# Pag5_Perifericos.net
KiCad netlist of a schematic drawn in Altium Designer
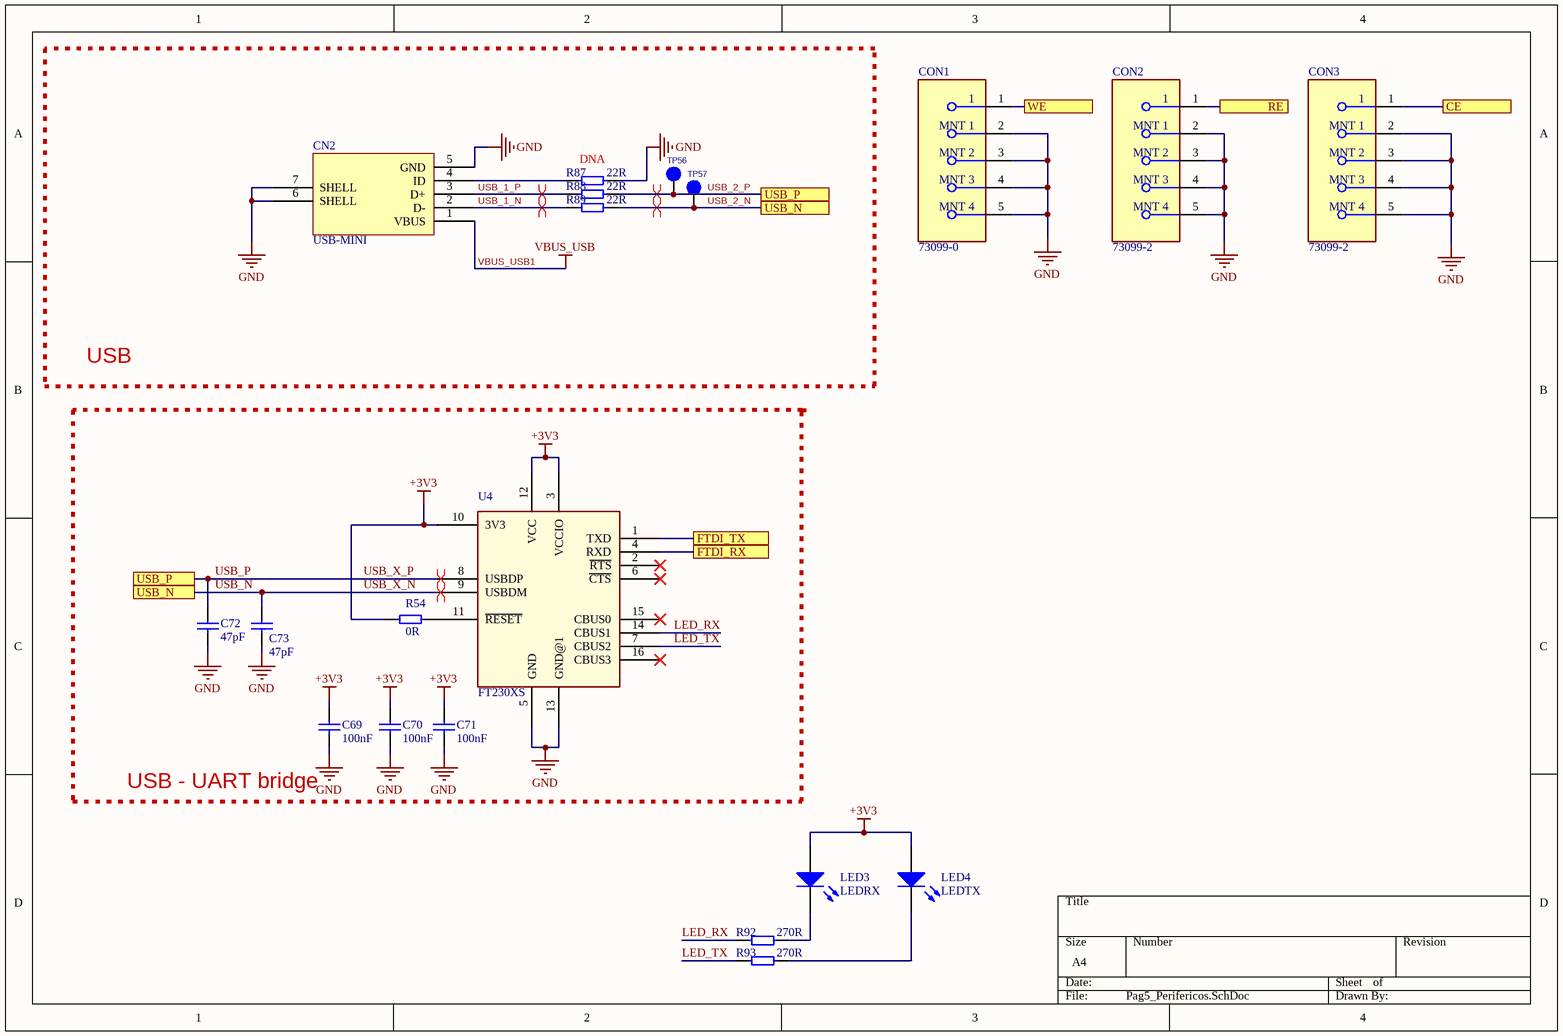
[diagram p0: Pag5_Perifericos.SchDoc]

(export (version "E")
  (design (tool "Eeschema 10.0.6"))
  (components
    (comp (ref "C69")
      (value "100nF")
      (footprint "0603")
      (description "Multilayer Ceramic Capacitors MLCC - SMD/SMT 100nF 16V 0603 10%")
      (fields (field (name "MANUFACTURER") "KEMET") (field (name "MPN") "C0603C104K4RACTU"))
      (libsource (lib "LIBSCH_PULLUP") (part "Cap"))
    )
    (comp (ref "C70")
      (value "100nF")
      (footprint "0603")
      (description "Multilayer Ceramic Capacitors MLCC - SMD/SMT 100nF 16V 0603 10%")
      (fields (field (name "MANUFACTURER") "KEMET") (field (name "MPN") "C0603C104K4RACTU"))
      (libsource (lib "LIBSCH_PULLUP") (part "Cap"))
    )
    (comp (ref "C71")
      (value "100nF")
      (footprint "0603")
      (description "Multilayer Ceramic Capacitors MLCC - SMD/SMT 100nF 16V 0603 10%")
      (fields (field (name "MANUFACTURER") "KEMET") (field (name "MPN") "C0603C104K4RACTU"))
      (libsource (lib "LIBSCH_PULLUP") (part "Cap"))
    )
    (comp (ref "C72")
      (value "47pF")
      (footprint "0603")
      (description "Multilayer Ceramic Capacitors MLCC - SMD/SMT 47pF 0603 25V 5%")
      (fields (field (name "MANUFACTURER") "Vishay") (field (name "MPN") "VJ0603A470JXXPW1BC"))
      (libsource (lib "LIBSCH_PULLUP") (part "Cap"))
    )
    (comp (ref "C73")
      (value "47pF")
      (footprint "0603")
      (description "Multilayer Ceramic Capacitors MLCC - SMD/SMT 47pF 0603 25V 5%")
      (fields (field (name "MANUFACTURER") "Vishay") (field (name "MPN") "VJ0603A470JXXPW1BC"))
      (libsource (lib "LIBSCH_PULLUP") (part "Cap"))
    )
    (comp (ref "CN2")
      (value "USB-MINI")
      (footprint "TE_2172034-1")
      (description "Standard LEDs - SMD 0603 SMT CHIP LED 572nm")
      (fields (field (name "MPN") "2172034-1") (field (name "MANUFACTURER") "TE Connectivity AMP Connectors"))
      (libsource (lib "LIBSCH_PULLUP") (part "USB-MINI"))
    )
    (comp (ref "CON1")
      (value "73099-0")
      (footprint "FP-73099-0-MFG")
      (description "R/A 4MM MOUNTG SAFE JACK/PCB BLK")
      (fields (field (name "MANUFACTURER") "Pomona Electronics"))
      (libsource (lib "Altium Content Vault") (part "a163d97a771fcdd2fd1f1a9264c171f"))
    )
    (comp (ref "CON2")
      (value "73099-2")
      (footprint "FP-73099-2-MFG")
      (description "R/A 4MM MOUNTG SAFE JACK/PCB RED")
      (fields (field (name "MANUFACTURER") "Pomona Electronics"))
      (libsource (lib "Altium Content Vault") (part "9c40ac4d87bbbe9fcb330bd20f98ca3"))
    )
    (comp (ref "CON3")
      (value "73099-2")
      (footprint "FP-73099-2-MFG")
      (description "R/A 4MM MOUNTG SAFE JACK/PCB RED")
      (fields (field (name "MANUFACTURER") "Pomona Electronics"))
      (libsource (lib "Altium Content Vault") (part "9c40ac4d87bbbe9fcb330bd20f98ca3"))
    )
    (comp (ref "LED3")
      (value "LEDRX")
      (footprint "0603 - LED")
      (description "Standard LEDs - SMD 0603 SMT CHIP LED 572nm")
      (fields (field (name "MANUFACTURER") "ROHM Semiconductor") (field (name "MPN") "SML-D13M8WT86"))
      (libsource (lib "LIBSCH_PULLUP") (part "LED"))
    )
    (comp (ref "LED4")
      (value "LEDTX")
      (footprint "0603 - LED")
      (description "Standard LEDs - SMD 0603 SMT CHIP LED 572nm")
      (fields (field (name "MANUFACTURER") "ROHM Semiconductor") (field (name "MPN") "SML-D13M8WT86"))
      (libsource (lib "LIBSCH_PULLUP") (part "LED"))
    )
    (comp (ref "R54")
      (value "0R")
      (footprint "0603")
      (description "Thick Film Resistors - SMD 0 Ohms 100 mW 0603 5%")
      (fields (field (name "MPN") "RC0603JR-070RL") (field (name "MANUFACTURER") "Yageo"))
      (libsource (lib "potenciostato") (part "Pullup_Res_0_0603_RES"))
    )
    (comp (ref "R87")
      (value "22R")
      (footprint "0603")
      (description "Thin Film Resistors - SMD 22Ohms 0603 100mW 1%")
      (fields
        (field (name "PCBA") "DNA")
        (field (name "MANUFACTURER") "Yageo")
        (field (name "MPN") "RT0603FRE0722RL")
      )
      (libsource (lib "") (part "Res_1"))
    )
    (comp (ref "R88")
      (value "22R")
      (footprint "0603")
      (description "Thin Film Resistors - SMD 22Ohms 0603 100mW 1%")
      (fields (field (name "MANUFACTURER") "Yageo") (field (name "MPN") "RT0603FRE0722RL"))
      (libsource (lib "") (part "Res_1"))
    )
    (comp (ref "R89")
      (value "22R")
      (footprint "0603")
      (description "Thin Film Resistors - SMD 22Ohms 0603 100mW 1%")
      (fields (field (name "MANUFACTURER") "Yageo") (field (name "MPN") "RT0603FRE0722RL"))
      (libsource (lib "") (part "Res_1"))
    )
    (comp (ref "R92")
      (value "270R")
      (footprint "0603")
      (description "Thick Film Resistors - SMD 270 Ohms 0603 100mW 1%")
      (fields (field (name "MANUFACTURER") "Yageo") (field (name "MPN") "RC0603FR-07270RL"))
      (libsource (lib "LIBSCH_PULLUP") (part "Res"))
    )
    (comp (ref "R93")
      (value "270R")
      (footprint "0603")
      (description "Thick Film Resistors - SMD 270 Ohms 0603 100mW 1%")
      (fields (field (name "MANUFACTURER") "Yageo") (field (name "MPN") "RC0603FR-07270RL"))
      (libsource (lib "LIBSCH_PULLUP") (part "Res"))
    )
    (comp (ref "TP56")
      (value "Test_Point")
      (footprint "TEST")
      (fields (field (name "MANUFACTURER") "DNA"))
      (libsource (lib "Database_Pullup") (part "TestLoop"))
    )
    (comp (ref "TP57")
      (value "Test_Point")
      (footprint "TEST")
      (fields (field (name "MANUFACTURER") "DNA"))
      (libsource (lib "Database_Pullup") (part "TestLoop"))
    )
    (comp (ref "U4")
      (value "FT230XS")
      (footprint "SSOP-16-2")
      (fields (field (name "MANUFACTURER") "FTDI"))
      (libsource (lib "LIBSCH_PULLUP") (part "FT230XS"))
    )
  )
  (nets
    (net (code "1") (name "+3V3") (class "Default")
      (node (ref "C69") (pin "2") (pinfunction "2_2") (pintype "passive"))
      (node (ref "C70") (pin "2") (pinfunction "2_2") (pintype "passive"))
      (node (ref "C71") (pin "2") (pinfunction "2_2") (pintype "passive"))
      (node (ref "LED3") (pin "1") (pinfunction "A_1") (pintype "passive"))
      (node (ref "LED4") (pin "1") (pinfunction "A_1") (pintype "passive"))
      (node (ref "R54") (pin "2") (pinfunction "2_2") (pintype "passive"))
      (node (ref "U4") (pin "10") (pinfunction "3V3_10") (pintype "open_collector"))
      (node (ref "U4") (pin "12") (pinfunction "VCC_12") (pintype "open_collector"))
      (node (ref "U4") (pin "3") (pinfunction "VCCIO_3") (pintype "open_collector"))
    )
    (net (code "2") (name "/CE") (class "Default")
      (node (ref "CON3") (pin "1") (pinfunction "1_1") (pintype "passive"))
    )
    (net (code "3") (name "/FTDI_RX") (class "Default")
      (node (ref "U4") (pin "4") (pinfunction "RXD_4") (pintype "open_collector"))
    )
    (net (code "4") (name "/FTDI_TX") (class "Default")
      (node (ref "U4") (pin "1") (pinfunction "TXD_1") (pintype "open_collector"))
    )
    (net (code "5") (name "/LED_RX") (class "Default")
      (node (ref "R92") (pin "1") (pinfunction "1_1") (pintype "passive"))
      (node (ref "U4") (pin "14") (pinfunction "CBUS1_14") (pintype "open_collector"))
    )
    (net (code "6") (name "/LED_TX") (class "Default")
      (node (ref "R93") (pin "1") (pinfunction "1_1") (pintype "passive"))
      (node (ref "U4") (pin "7") (pinfunction "CBUS2_7") (pintype "open_collector"))
    )
    (net (code "7") (name "/RE") (class "Default")
      (node (ref "CON2") (pin "1") (pinfunction "1_1") (pintype "passive"))
    )
    (net (code "8") (name "/USB_1_N") (class "Default")
      (node (ref "CN2") (pin "2") (pinfunction "D-_2") (pintype "passive"))
      (node (ref "R89") (pin "2") (pinfunction "2_2") (pintype "passive"))
    )
    (net (code "9") (name "/USB_1_P") (class "Default")
      (node (ref "CN2") (pin "3") (pinfunction "D+_3") (pintype "passive"))
      (node (ref "R88") (pin "2") (pinfunction "2_2") (pintype "passive"))
    )
    (net (code "10") (name "/USB_2_N") (class "Default")
      (node (ref "C73") (pin "2") (pinfunction "2_2") (pintype "passive"))
      (node (ref "R89") (pin "1") (pinfunction "1_1") (pintype "passive"))
      (node (ref "TP57") (pin "1") (pinfunction "Pin1_1") (pintype "passive"))
      (node (ref "U4") (pin "9") (pinfunction "USBDM_9") (pintype "open_collector"))
    )
    (net (code "11") (name "/USB_2_P") (class "Default")
      (node (ref "C72") (pin "2") (pinfunction "2_2") (pintype "passive"))
      (node (ref "R88") (pin "1") (pinfunction "1_1") (pintype "passive"))
      (node (ref "TP56") (pin "1") (pinfunction "Pin1_1") (pintype "passive"))
      (node (ref "U4") (pin "8") (pinfunction "USBDP_8") (pintype "open_collector"))
    )
    (net (code "12") (name "/WE") (class "Default")
      (node (ref "CON1") (pin "1") (pinfunction "1_1") (pintype "passive"))
    )
    (net (code "13") (name "GND") (class "Default")
      (node (ref "C69") (pin "1") (pinfunction "1_1") (pintype "passive"))
      (node (ref "C70") (pin "1") (pinfunction "1_1") (pintype "passive"))
      (node (ref "C71") (pin "1") (pinfunction "1_1") (pintype "passive"))
      (node (ref "C72") (pin "1") (pinfunction "1_1") (pintype "passive"))
      (node (ref "C73") (pin "1") (pinfunction "1_1") (pintype "passive"))
      (node (ref "CN2") (pin "5") (pinfunction "GND_5") (pintype "passive"))
      (node (ref "CN2") (pin "6") (pinfunction "SHELL_6") (pintype "passive"))
      (node (ref "CN2") (pin "7") (pinfunction "SHELL_7") (pintype "passive"))
      (node (ref "CON1") (pin "2") (pinfunction "MNT_1_2") (pintype "passive"))
      (node (ref "CON1") (pin "3") (pinfunction "MNT_2_3") (pintype "passive"))
      (node (ref "CON1") (pin "4") (pinfunction "MNT_3_4") (pintype "passive"))
      (node (ref "CON1") (pin "5") (pinfunction "MNT_4_5") (pintype "passive"))
      (node (ref "CON2") (pin "2") (pinfunction "MNT_1_2") (pintype "passive"))
      (node (ref "CON2") (pin "3") (pinfunction "MNT_2_3") (pintype "passive"))
      (node (ref "CON2") (pin "4") (pinfunction "MNT_3_4") (pintype "passive"))
      (node (ref "CON2") (pin "5") (pinfunction "MNT_4_5") (pintype "passive"))
      (node (ref "CON3") (pin "2") (pinfunction "MNT_1_2") (pintype "passive"))
      (node (ref "CON3") (pin "3") (pinfunction "MNT_2_3") (pintype "passive"))
      (node (ref "CON3") (pin "4") (pinfunction "MNT_3_4") (pintype "passive"))
      (node (ref "CON3") (pin "5") (pinfunction "MNT_4_5") (pintype "passive"))
      (node (ref "R87") (pin "1") (pinfunction "1_1") (pintype "passive"))
      (node (ref "U4") (pin "13") (pinfunction "GND@1_13") (pintype "open_collector"))
      (node (ref "U4") (pin "5") (pinfunction "GND_5") (pintype "open_collector"))
    )
    (net (code "14") (name "Net-(CN2-ID)") (class "Default")
      (node (ref "CN2") (pin "4") (pinfunction "ID_4") (pintype "passive"))
      (node (ref "R87") (pin "2") (pinfunction "2_2") (pintype "passive"))
    )
    (net (code "15") (name "Net-(LED3-K)") (class "Default")
      (node (ref "LED3") (pin "2") (pinfunction "K_2") (pintype "passive"))
      (node (ref "R92") (pin "2") (pinfunction "2_2") (pintype "passive"))
    )
    (net (code "16") (name "Net-(LED4-K)") (class "Default")
      (node (ref "LED4") (pin "2") (pinfunction "K_2") (pintype "passive"))
      (node (ref "R93") (pin "2") (pinfunction "2_2") (pintype "passive"))
    )
    (net (code "17") (name "Net-(U4-~{RESET})") (class "Default")
      (node (ref "R54") (pin "1") (pinfunction "1_1") (pintype "passive"))
      (node (ref "U4") (pin "11") (pinfunction "~{RESET}_11") (pintype "open_collector"))
    )
    (net (code "18") (name "VBUS_USB") (class "Default")
      (node (ref "CN2") (pin "1") (pinfunction "VBUS_1") (pintype "passive"))
    )
    (net (code "19") (name "unconnected-(U4-CBUS0-Pad15)") (class "Default")
      (node (ref "U4") (pin "15") (pinfunction "CBUS0_15") (pintype "open_collector+no_connect"))
    )
    (net (code "20") (name "unconnected-(U4-CBUS3-Pad16)") (class "Default")
      (node (ref "U4") (pin "16") (pinfunction "CBUS3_16") (pintype "open_collector+no_connect"))
    )
    (net (code "21") (name "unconnected-(U4-~{CTS}-Pad6)") (class "Default")
      (node (ref "U4") (pin "6") (pinfunction "~{CTS}_6") (pintype "open_collector+no_connect"))
    )
    (net (code "22") (name "unconnected-(U4-~{RTS}-Pad2)") (class "Default")
      (node (ref "U4") (pin "2") (pinfunction "~{RTS}_2") (pintype "open_collector+no_connect"))
    )
  )
)
